# SparkFun-MicroViewUSB.net
KiCad netlist of a schematic drawn in EAGLE
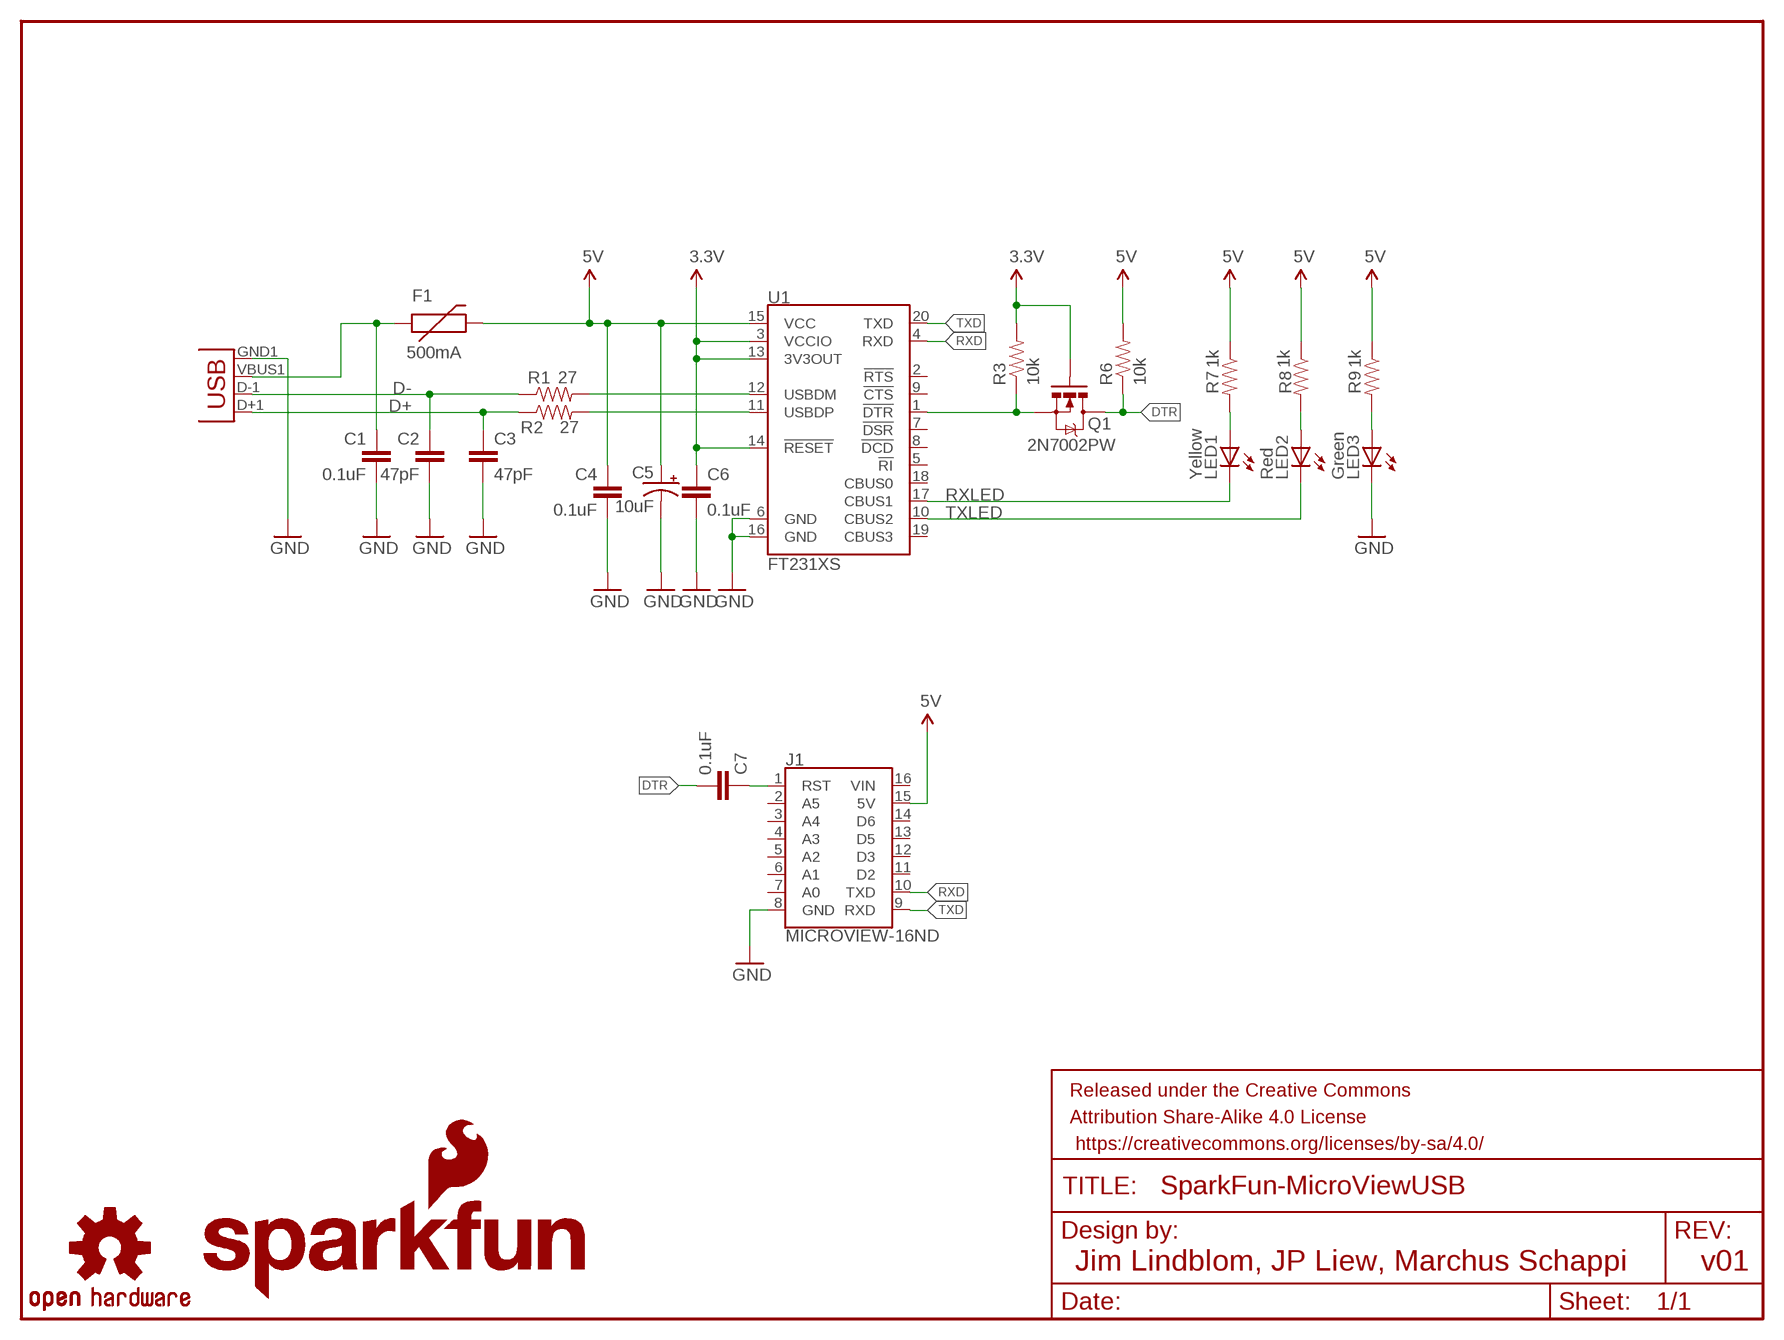
[diagram p0: schematic, sheet 1]

(export (version "E")
  (design (tool "Eeschema 10.0.6"))
  (components
    (comp (ref "C1")
      (value "0.1uF")
      (footprint "eagle-import:0603-CAP")
      (libsource (lib "eagle-import") (part "CAP0603-CAP"))
    )
    (comp (ref "C2")
      (value "47pF")
      (footprint "eagle-import:0603-CAP")
      (libsource (lib "eagle-import") (part "47PF-50V-5%(0603)"))
    )
    (comp (ref "C3")
      (value "47pF")
      (footprint "eagle-import:0603-CAP")
      (libsource (lib "eagle-import") (part "47PF-50V-5%(0603)"))
    )
    (comp (ref "C4")
      (value "0.1uF")
      (footprint "eagle-import:0603-CAP")
      (libsource (lib "eagle-import") (part "CAP0603-CAP"))
    )
    (comp (ref "C5")
      (value "10uF")
      (footprint "eagle-import:EIA3216")
      (libsource (lib "eagle-import") (part "CAP_POL1206"))
    )
    (comp (ref "C6")
      (value "0.1uF")
      (footprint "eagle-import:0603-CAP")
      (libsource (lib "eagle-import") (part "CAP0603-CAP"))
    )
    (comp (ref "C7")
      (value "0.1uF")
      (footprint "eagle-import:0603-CAP")
      (libsource (lib "eagle-import") (part "0.1UF-25V(+80/-20%)(0603)"))
    )
    (comp (ref "F1")
      (value "500mA")
      (footprint "eagle-import:PTC-1206")
      (libsource (lib "eagle-import") (part "PTCSMD"))
    )
    (comp (ref "FRAME1")
      (value "FRAME-LETTER")
      (footprint "eagle-import:CREATIVE_COMMONS")
      (libsource (lib "eagle-import") (part "FRAME-LETTER"))
    )
    (comp (ref "J1")
      (value "MICROVIEW-16ND")
      (footprint "eagle-import:MV-DIP16-NODIMENSION")
      (libsource (lib "eagle-import") (part "MICROVIEW-16ND"))
    )
    (comp (ref "JP2")
      (value "USBA-SMD-MALE")
      (footprint "eagle-import:USB-A-SMT-MALE")
      (libsource (lib "eagle-import") (part "USBA-SMD-MALE"))
    )
    (comp (ref "LED1")
      (value "Yellow")
      (footprint "eagle-import:LED-1206")
      (libsource (lib "eagle-import") (part "LED1206"))
    )
    (comp (ref "LED2")
      (value "Red")
      (footprint "eagle-import:LED-1206")
      (libsource (lib "eagle-import") (part "LED1206"))
    )
    (comp (ref "LED3")
      (value "Green")
      (footprint "eagle-import:LED-1206")
      (libsource (lib "eagle-import") (part "LED1206"))
    )
    (comp (ref "LOGO1")
      (value "OSHW-LOGOS")
      (footprint "eagle-import:OSHW-LOGO-S")
      (libsource (lib "eagle-import") (part "OSHW-LOGOS"))
    )
    (comp (ref "LOGO2")
      (value "SFE_LOGO_FLAME.1_INCH")
      (footprint "eagle-import:SFE_LOGO_FLAME_.1")
      (libsource (lib "eagle-import") (part "SFE_LOGO_FLAME.1_INCH"))
    )
    (comp (ref "LOGO3")
      (value "SFE_LOGO_NAME_FLAME.1_INCH")
      (footprint "eagle-import:SFE_LOGO_NAME_FLAME_.1")
      (libsource (lib "eagle-import") (part "SFE_LOGO_NAME_FLAME.1_INCH"))
    )
    (comp (ref "Q1")
      (value "2N7002PW")
      (footprint "eagle-import:SOT323")
      (libsource (lib "eagle-import") (part "MOSFET-NCHANNEL2N7002PW"))
    )
    (comp (ref "R1")
      (value "27")
      (footprint "eagle-import:0603-RES")
      (libsource (lib "eagle-import") (part "SparkFun-Resistors_RESISTOR0603-RES"))
    )
    (comp (ref "R2")
      (value "27")
      (footprint "eagle-import:0603-RES")
      (libsource (lib "eagle-import") (part "SparkFun-Resistors_RESISTOR0603-RES"))
    )
    (comp (ref "R3")
      (value "10k")
      (footprint "eagle-import:0603-RES")
      (libsource (lib "eagle-import") (part "RESISTOR0603-RES"))
    )
    (comp (ref "R6")
      (value "10k")
      (footprint "eagle-import:0603-RES")
      (libsource (lib "eagle-import") (part "RESISTOR0603-RES"))
    )
    (comp (ref "R7")
      (value "1k")
      (footprint "eagle-import:0603-RES")
      (libsource (lib "eagle-import") (part "RESISTOR0603-RES"))
    )
    (comp (ref "R8")
      (value "1k")
      (footprint "eagle-import:0603-RES")
      (libsource (lib "eagle-import") (part "RESISTOR0603-RES"))
    )
    (comp (ref "R9")
      (value "1k")
      (footprint "eagle-import:0603-RES")
      (libsource (lib "eagle-import") (part "RESISTOR0603-RES"))
    )
    (comp (ref "U1")
      (value "FT231XS")
      (footprint "eagle-import:SSOP20_L")
      (libsource (lib "eagle-import") (part "FT231XS"))
    )
  )
  (nets
    (net (code "1") (name "/D+") (class "Default")
      (node (ref "C3") (pin "1") (pinfunction "1_1") (pintype "passive"))
      (node (ref "JP2") (pin "D+1") (pinfunction "D+_D+1") (pintype "bidirectional"))
      (node (ref "R2") (pin "1") (pinfunction "1_1") (pintype "passive"))
    )
    (net (code "2") (name "/D-") (class "Default")
      (node (ref "C2") (pin "1") (pinfunction "1_1") (pintype "passive"))
      (node (ref "JP2") (pin "D-1") (pinfunction "D-_D-1") (pintype "bidirectional"))
      (node (ref "R1") (pin "1") (pinfunction "1_1") (pintype "passive"))
    )
    (net (code "3") (name "/RXLED") (class "Default")
      (node (ref "LED1") (pin "C") (pinfunction "C_C") (pintype "passive"))
      (node (ref "U1") (pin "17") (pinfunction "CBUS1_17") (pintype "bidirectional"))
    )
    (net (code "4") (name "/TXLED") (class "Default")
      (node (ref "LED2") (pin "C") (pinfunction "C_C") (pintype "passive"))
      (node (ref "U1") (pin "10") (pinfunction "CBUS2_10") (pintype "bidirectional"))
    )
    (net (code "5") (name "3.3V") (class "Default")
      (node (ref "C6") (pin "1") (pinfunction "1_1") (pintype "passive"))
      (node (ref "Q1") (pin "1") (pinfunction "G_1") (pintype "passive"))
      (node (ref "R3") (pin "2") (pinfunction "2_2") (pintype "passive"))
      (node (ref "U1") (pin "13") (pinfunction "3V3OUT_13") (pintype "bidirectional"))
      (node (ref "U1") (pin "14") (pinfunction "~{RESET}_14") (pintype "bidirectional"))
      (node (ref "U1") (pin "3") (pinfunction "VCCIO_3") (pintype "bidirectional"))
    )
    (net (code "6") (name "5V") (class "Default")
      (node (ref "C4") (pin "1") (pinfunction "1_1") (pintype "passive"))
      (node (ref "C5") (pin "A") (pinfunction "+_A") (pintype "passive"))
      (node (ref "F1") (pin "2") (pinfunction "2_2") (pintype "bidirectional"))
      (node (ref "J1") (pin "15") (pinfunction "5V_15") (pintype "output"))
      (node (ref "R6") (pin "2") (pinfunction "2_2") (pintype "passive"))
      (node (ref "R7") (pin "1") (pinfunction "1_1") (pintype "passive"))
      (node (ref "R8") (pin "1") (pinfunction "1_1") (pintype "passive"))
      (node (ref "R9") (pin "1") (pinfunction "1_1") (pintype "passive"))
      (node (ref "U1") (pin "15") (pinfunction "VCC_15") (pintype "bidirectional"))
    )
    (net (code "7") (name "DTR") (class "Default")
      (node (ref "C7") (pin "2") (pinfunction "2_2") (pintype "passive"))
      (node (ref "Q1") (pin "3") (pinfunction "D_3") (pintype "passive"))
      (node (ref "R6") (pin "1") (pinfunction "1_1") (pintype "passive"))
    )
    (net (code "8") (name "GND") (class "Default")
      (node (ref "C1") (pin "2") (pinfunction "2_2") (pintype "passive"))
      (node (ref "C2") (pin "2") (pinfunction "2_2") (pintype "passive"))
      (node (ref "C3") (pin "2") (pinfunction "2_2") (pintype "passive"))
      (node (ref "C4") (pin "2") (pinfunction "2_2") (pintype "passive"))
      (node (ref "C5") (pin "C") (pinfunction "-_C") (pintype "passive"))
      (node (ref "C6") (pin "2") (pinfunction "2_2") (pintype "passive"))
      (node (ref "J1") (pin "8") (pinfunction "GND_8") (pintype "output"))
      (node (ref "JP2") (pin "GND1") (pinfunction "GND_GND1") (pintype "bidirectional"))
      (node (ref "LED3") (pin "C") (pinfunction "C_C") (pintype "passive"))
      (node (ref "U1") (pin "16") (pinfunction "GND_16") (pintype "bidirectional"))
      (node (ref "U1") (pin "6") (pinfunction "GND_6") (pintype "bidirectional"))
    )
    (net (code "9") (name "Net-(J1-RST)") (class "Default")
      (node (ref "C7") (pin "1") (pinfunction "1_1") (pintype "passive"))
      (node (ref "J1") (pin "1") (pinfunction "RST_1") (pintype "output"))
    )
    (net (code "10") (name "Net-(JP2-VBUS)") (class "Default")
      (node (ref "C1") (pin "1") (pinfunction "1_1") (pintype "passive"))
      (node (ref "F1") (pin "1") (pinfunction "1_1") (pintype "bidirectional"))
      (node (ref "JP2") (pin "VBUS1") (pinfunction "VBUS_VBUS1") (pintype "bidirectional"))
    )
    (net (code "11") (name "Net-(LED1-PadA)") (class "Default")
      (node (ref "LED1") (pin "A") (pinfunction "A_A") (pintype "passive"))
      (node (ref "R7") (pin "2") (pinfunction "2_2") (pintype "passive"))
    )
    (net (code "12") (name "Net-(LED2-PadA)") (class "Default")
      (node (ref "LED2") (pin "A") (pinfunction "A_A") (pintype "passive"))
      (node (ref "R8") (pin "2") (pinfunction "2_2") (pintype "passive"))
    )
    (net (code "13") (name "Net-(LED3-PadA)") (class "Default")
      (node (ref "LED3") (pin "A") (pinfunction "A_A") (pintype "passive"))
      (node (ref "R9") (pin "2") (pinfunction "2_2") (pintype "passive"))
    )
    (net (code "14") (name "Net-(Q1-S)") (class "Default")
      (node (ref "Q1") (pin "2") (pinfunction "S_2") (pintype "passive"))
      (node (ref "R3") (pin "1") (pinfunction "1_1") (pintype "passive"))
      (node (ref "U1") (pin "1") (pinfunction "~{DTR}_1") (pintype "bidirectional"))
    )
    (net (code "15") (name "Net-(U1-USBDM)") (class "Default")
      (node (ref "R1") (pin "2") (pinfunction "2_2") (pintype "passive"))
      (node (ref "U1") (pin "12") (pinfunction "USBDM_12") (pintype "bidirectional"))
    )
    (net (code "16") (name "Net-(U1-USBDP)") (class "Default")
      (node (ref "R2") (pin "2") (pinfunction "2_2") (pintype "passive"))
      (node (ref "U1") (pin "11") (pinfunction "USBDP_11") (pintype "bidirectional"))
    )
    (net (code "17") (name "RXD") (class "Default")
      (node (ref "J1") (pin "10") (pinfunction "TXD_10") (pintype "output"))
      (node (ref "U1") (pin "4") (pinfunction "RXD_4") (pintype "bidirectional"))
    )
    (net (code "18") (name "TXD") (class "Default")
      (node (ref "J1") (pin "9") (pinfunction "RXD_9") (pintype "output"))
      (node (ref "U1") (pin "20") (pinfunction "TXD_20") (pintype "bidirectional"))
    )
    (net (code "19") (name "unconnected-(J1-A0-Pad7)") (class "Default")
      (node (ref "J1") (pin "7") (pinfunction "A0_7") (pintype "output"))
    )
    (net (code "20") (name "unconnected-(J1-A1-Pad6)") (class "Default")
      (node (ref "J1") (pin "6") (pinfunction "A1_6") (pintype "output"))
    )
    (net (code "21") (name "unconnected-(J1-A2-Pad5)") (class "Default")
      (node (ref "J1") (pin "5") (pinfunction "A2_5") (pintype "output"))
    )
    (net (code "22") (name "unconnected-(J1-A3-Pad4)") (class "Default")
      (node (ref "J1") (pin "4") (pinfunction "A3_4") (pintype "output"))
    )
    (net (code "23") (name "unconnected-(J1-A4-Pad3)") (class "Default")
      (node (ref "J1") (pin "3") (pinfunction "A4_3") (pintype "output"))
    )
    (net (code "24") (name "unconnected-(J1-A5-Pad2)") (class "Default")
      (node (ref "J1") (pin "2") (pinfunction "A5_2") (pintype "output"))
    )
    (net (code "25") (name "unconnected-(J1-D2-Pad11)") (class "Default")
      (node (ref "J1") (pin "11") (pinfunction "D2_11") (pintype "output"))
    )
    (net (code "26") (name "unconnected-(J1-D3-Pad12)") (class "Default")
      (node (ref "J1") (pin "12") (pinfunction "D3_12") (pintype "output"))
    )
    (net (code "27") (name "unconnected-(J1-D5-Pad13)") (class "Default")
      (node (ref "J1") (pin "13") (pinfunction "D5_13") (pintype "output"))
    )
    (net (code "28") (name "unconnected-(J1-D6-Pad14)") (class "Default")
      (node (ref "J1") (pin "14") (pinfunction "D6_14") (pintype "output"))
    )
    (net (code "29") (name "unconnected-(J1-VIN-Pad16)") (class "Default")
      (node (ref "J1") (pin "16") (pinfunction "VIN_16") (pintype "output"))
    )
    (net (code "30") (name "unconnected-(U1-CBUS0-Pad18)") (class "Default")
      (node (ref "U1") (pin "18") (pinfunction "CBUS0_18") (pintype "bidirectional"))
    )
    (net (code "31") (name "unconnected-(U1-CBUS3-Pad19)") (class "Default")
      (node (ref "U1") (pin "19") (pinfunction "CBUS3_19") (pintype "bidirectional"))
    )
    (net (code "32") (name "unconnected-(U1-~{CTS}-Pad9)") (class "Default")
      (node (ref "U1") (pin "9") (pinfunction "~{CTS}_9") (pintype "bidirectional"))
    )
    (net (code "33") (name "unconnected-(U1-~{DCD}-Pad8)") (class "Default")
      (node (ref "U1") (pin "8") (pinfunction "~{DCD}_8") (pintype "bidirectional"))
    )
    (net (code "34") (name "unconnected-(U1-~{DSR}-Pad7)") (class "Default")
      (node (ref "U1") (pin "7") (pinfunction "~{DSR}_7") (pintype "bidirectional"))
    )
    (net (code "35") (name "unconnected-(U1-~{RI}-Pad5)") (class "Default")
      (node (ref "U1") (pin "5") (pinfunction "~{RI}_5") (pintype "bidirectional"))
    )
    (net (code "36") (name "unconnected-(U1-~{RTS}-Pad2)") (class "Default")
      (node (ref "U1") (pin "2") (pinfunction "~{RTS}_2") (pintype "bidirectional"))
    )
  )
)
